# cicely_A_v1.net
KiCad netlist of a schematic drawn in EAGLE
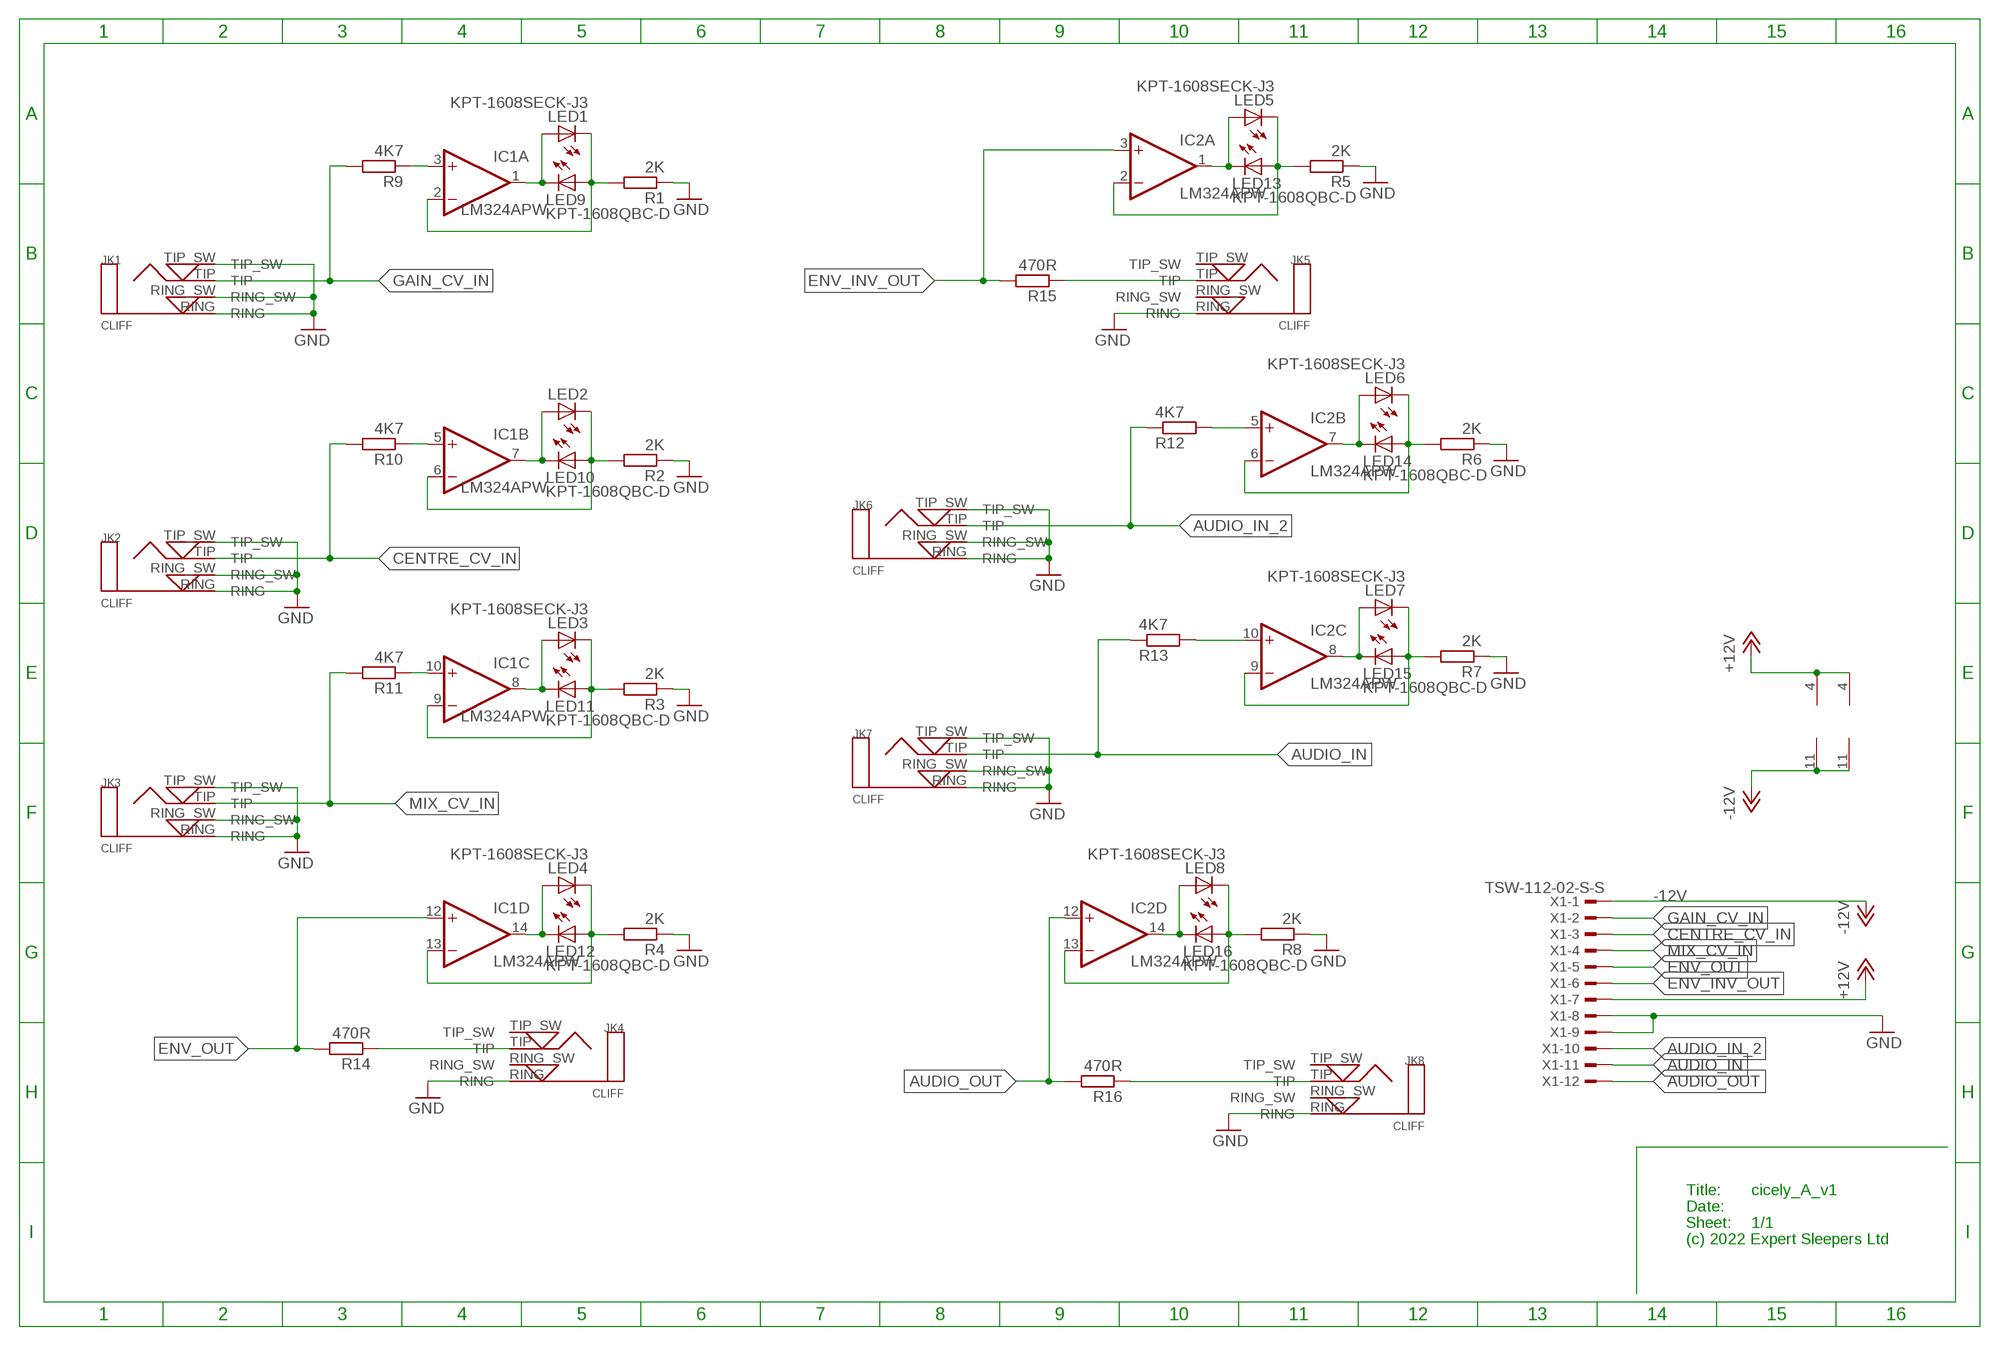
[diagram p0: schematic, sheet 1]

(export (version "E")
  (design (tool "Eeschema 10.0.6"))
  (components
    (comp (ref "IC1")
      (value "LM324APW")
      (footprint "eagle-import:PW_R-PDSO-G14")
      (libsource (lib "eagle-import") (part "TL074PW"))
    )
    (comp (ref "IC2")
      (value "LM324APW")
      (footprint "eagle-import:PW_R-PDSO-G14")
      (libsource (lib "eagle-import") (part "TL074PW"))
    )
    (comp (ref "JK1")
      (value "CLIFF")
      (footprint "eagle-import:CLIFF3.5MMPCB")
      (libsource (lib "eagle-import") (part "CLIFF3.5MM_PCB_SW_JK"))
    )
    (comp (ref "JK2")
      (value "CLIFF")
      (footprint "eagle-import:CLIFF3.5MMPCB")
      (libsource (lib "eagle-import") (part "CLIFF3.5MM_PCB_SW_JK"))
    )
    (comp (ref "JK3")
      (value "CLIFF")
      (footprint "eagle-import:CLIFF3.5MMPCB")
      (libsource (lib "eagle-import") (part "CLIFF3.5MM_PCB_SW_JK"))
    )
    (comp (ref "JK4")
      (value "CLIFF")
      (footprint "eagle-import:CLIFF3.5MMPCB")
      (libsource (lib "eagle-import") (part "CLIFF3.5MM_PCB_SW_JK"))
    )
    (comp (ref "JK5")
      (value "CLIFF")
      (footprint "eagle-import:CLIFF3.5MMPCB")
      (libsource (lib "eagle-import") (part "CLIFF3.5MM_PCB_SW_JK"))
    )
    (comp (ref "JK6")
      (value "CLIFF")
      (footprint "eagle-import:CLIFF3.5MMPCB")
      (libsource (lib "eagle-import") (part "CLIFF3.5MM_PCB_SW_JK"))
    )
    (comp (ref "JK7")
      (value "CLIFF")
      (footprint "eagle-import:CLIFF3.5MMPCB")
      (libsource (lib "eagle-import") (part "CLIFF3.5MM_PCB_SW_JK"))
    )
    (comp (ref "JK8")
      (value "CLIFF")
      (footprint "eagle-import:CLIFF3.5MMPCB")
      (libsource (lib "eagle-import") (part "CLIFF3.5MM_PCB_SW_JK"))
    )
    (comp (ref "LED1")
      (value "KPT-1608SECK-J3")
      (footprint "eagle-import:CHIPLED_0603_LEFT")
      (libsource (lib "eagle-import") (part "KPT-1608SECK-J3"))
    )
    (comp (ref "LED2")
      (value "KPT-1608SECK-J3")
      (footprint "eagle-import:CHIPLED_0603_LEFT")
      (libsource (lib "eagle-import") (part "KPT-1608SECK-J3"))
    )
    (comp (ref "LED3")
      (value "KPT-1608SECK-J3")
      (footprint "eagle-import:CHIPLED_0603_LEFT")
      (libsource (lib "eagle-import") (part "KPT-1608SECK-J3"))
    )
    (comp (ref "LED4")
      (value "KPT-1608SECK-J3")
      (footprint "eagle-import:CHIPLED_0603_LEFT")
      (libsource (lib "eagle-import") (part "KPT-1608SECK-J3"))
    )
    (comp (ref "LED5")
      (value "KPT-1608SECK-J3")
      (footprint "eagle-import:CHIPLED_0603_LEFT")
      (libsource (lib "eagle-import") (part "KPT-1608SECK-J3"))
    )
    (comp (ref "LED6")
      (value "KPT-1608SECK-J3")
      (footprint "eagle-import:CHIPLED_0603_LEFT")
      (libsource (lib "eagle-import") (part "KPT-1608SECK-J3"))
    )
    (comp (ref "LED7")
      (value "KPT-1608SECK-J3")
      (footprint "eagle-import:CHIPLED_0603_LEFT")
      (libsource (lib "eagle-import") (part "KPT-1608SECK-J3"))
    )
    (comp (ref "LED8")
      (value "KPT-1608SECK-J3")
      (footprint "eagle-import:CHIPLED_0603_LEFT")
      (libsource (lib "eagle-import") (part "KPT-1608SECK-J3"))
    )
    (comp (ref "LED9")
      (value "KPT-1608QBC-D")
      (footprint "eagle-import:CHIPLED_0603_RIGHT")
      (libsource (lib "eagle-import") (part "KPT-1608QBC-D"))
    )
    (comp (ref "LED10")
      (value "KPT-1608QBC-D")
      (footprint "eagle-import:CHIPLED_0603_RIGHT")
      (libsource (lib "eagle-import") (part "KPT-1608QBC-D"))
    )
    (comp (ref "LED11")
      (value "KPT-1608QBC-D")
      (footprint "eagle-import:CHIPLED_0603_RIGHT")
      (libsource (lib "eagle-import") (part "KPT-1608QBC-D"))
    )
    (comp (ref "LED12")
      (value "KPT-1608QBC-D")
      (footprint "eagle-import:CHIPLED_0603_RIGHT")
      (libsource (lib "eagle-import") (part "KPT-1608QBC-D"))
    )
    (comp (ref "LED13")
      (value "KPT-1608QBC-D")
      (footprint "eagle-import:CHIPLED_0603_RIGHT")
      (libsource (lib "eagle-import") (part "KPT-1608QBC-D"))
    )
    (comp (ref "LED14")
      (value "KPT-1608QBC-D")
      (footprint "eagle-import:CHIPLED_0603_RIGHT")
      (libsource (lib "eagle-import") (part "KPT-1608QBC-D"))
    )
    (comp (ref "LED15")
      (value "KPT-1608QBC-D")
      (footprint "eagle-import:CHIPLED_0603_RIGHT")
      (libsource (lib "eagle-import") (part "KPT-1608QBC-D"))
    )
    (comp (ref "LED16")
      (value "KPT-1608QBC-D")
      (footprint "eagle-import:CHIPLED_0603_RIGHT")
      (libsource (lib "eagle-import") (part "KPT-1608QBC-D"))
    )
    (comp (ref "R1")
      (value "2K")
      (footprint "eagle-import:R1206")
      (libsource (lib "eagle-import") (part "R-EU_R1206"))
    )
    (comp (ref "R2")
      (value "2K")
      (footprint "eagle-import:R1206")
      (libsource (lib "eagle-import") (part "R-EU_R1206"))
    )
    (comp (ref "R3")
      (value "2K")
      (footprint "eagle-import:R1206")
      (libsource (lib "eagle-import") (part "R-EU_R1206"))
    )
    (comp (ref "R4")
      (value "2K")
      (footprint "eagle-import:R1206")
      (libsource (lib "eagle-import") (part "R-EU_R1206"))
    )
    (comp (ref "R5")
      (value "2K")
      (footprint "eagle-import:R1206")
      (libsource (lib "eagle-import") (part "R-EU_R1206"))
    )
    (comp (ref "R6")
      (value "2K")
      (footprint "eagle-import:R1206")
      (libsource (lib "eagle-import") (part "R-EU_R1206"))
    )
    (comp (ref "R7")
      (value "2K")
      (footprint "eagle-import:R1206")
      (libsource (lib "eagle-import") (part "R-EU_R1206"))
    )
    (comp (ref "R8")
      (value "2K")
      (footprint "eagle-import:R1206")
      (libsource (lib "eagle-import") (part "R-EU_R1206"))
    )
    (comp (ref "R9")
      (value "4K7")
      (footprint "eagle-import:R1206")
      (libsource (lib "eagle-import") (part "R-EU_R1206"))
    )
    (comp (ref "R10")
      (value "4K7")
      (footprint "eagle-import:R1206")
      (libsource (lib "eagle-import") (part "R-EU_R1206"))
    )
    (comp (ref "R11")
      (value "4K7")
      (footprint "eagle-import:R1206")
      (libsource (lib "eagle-import") (part "R-EU_R1206"))
    )
    (comp (ref "R12")
      (value "4K7")
      (footprint "eagle-import:R1206")
      (libsource (lib "eagle-import") (part "R-EU_R1206"))
    )
    (comp (ref "R13")
      (value "4K7")
      (footprint "eagle-import:R1206")
      (libsource (lib "eagle-import") (part "R-EU_R1206"))
    )
    (comp (ref "R14")
      (value "470R")
      (footprint "eagle-import:R1206")
      (libsource (lib "eagle-import") (part "R-EU_R1206"))
    )
    (comp (ref "R15")
      (value "470R")
      (footprint "eagle-import:R1206")
      (libsource (lib "eagle-import") (part "R-EU_R1206"))
    )
    (comp (ref "R16")
      (value "470R")
      (footprint "eagle-import:R1206")
      (libsource (lib "eagle-import") (part "R-EU_R1206"))
    )
    (comp (ref "X1")
      (value "TSW-112-02-S-S")
      (footprint "eagle-import:TSW-112-02-S-S")
      (libsource (lib "eagle-import") (part "TSW-112-02-S-S"))
    )
  )
  (nets
    (net (code "1") (name "+12V") (class "Default")
      (node (ref "IC1") (pin "4") (pinfunction "V+_4") (pintype "power_in"))
      (node (ref "IC2") (pin "4") (pinfunction "V+_4") (pintype "power_in"))
      (node (ref "X1") (pin "7") (pinfunction "1_7") (pintype "passive"))
    )
    (net (code "2") (name "-12V") (class "Default")
      (node (ref "IC1") (pin "11") (pinfunction "V-_11") (pintype "power_in"))
      (node (ref "IC2") (pin "11") (pinfunction "V-_11") (pintype "power_in"))
      (node (ref "X1") (pin "1") (pinfunction "1_1") (pintype "passive"))
    )
    (net (code "3") (name "AUDIO_IN") (class "Default")
      (node (ref "JK7") (pin "TIP") (pinfunction "TIP_TIP") (pintype "bidirectional"))
      (node (ref "R13") (pin "1") (pinfunction "1_1") (pintype "passive"))
      (node (ref "X1") (pin "11") (pinfunction "1_11") (pintype "passive"))
    )
    (net (code "4") (name "AUDIO_IN_2") (class "Default")
      (node (ref "JK6") (pin "TIP") (pinfunction "TIP_TIP") (pintype "bidirectional"))
      (node (ref "R12") (pin "1") (pinfunction "1_1") (pintype "passive"))
      (node (ref "X1") (pin "10") (pinfunction "1_10") (pintype "passive"))
    )
    (net (code "5") (name "AUDIO_OUT") (class "Default")
      (node (ref "IC2") (pin "12") (pinfunction "+IN_12") (pintype "input"))
      (node (ref "R16") (pin "2") (pinfunction "2_2") (pintype "passive"))
      (node (ref "X1") (pin "12") (pinfunction "1_12") (pintype "passive"))
    )
    (net (code "6") (name "CENTRE_CV_IN") (class "Default")
      (node (ref "JK2") (pin "TIP") (pinfunction "TIP_TIP") (pintype "bidirectional"))
      (node (ref "R10") (pin "2") (pinfunction "2_2") (pintype "passive"))
      (node (ref "X1") (pin "3") (pinfunction "1_3") (pintype "passive"))
    )
    (net (code "7") (name "ENV_INV_OUT") (class "Default")
      (node (ref "IC2") (pin "3") (pinfunction "+IN_3") (pintype "input"))
      (node (ref "R15") (pin "2") (pinfunction "2_2") (pintype "passive"))
      (node (ref "X1") (pin "6") (pinfunction "1_6") (pintype "passive"))
    )
    (net (code "8") (name "ENV_OUT") (class "Default")
      (node (ref "IC1") (pin "12") (pinfunction "+IN_12") (pintype "input"))
      (node (ref "R14") (pin "2") (pinfunction "2_2") (pintype "passive"))
      (node (ref "X1") (pin "5") (pinfunction "1_5") (pintype "passive"))
    )
    (net (code "9") (name "GAIN_CV_IN") (class "Default")
      (node (ref "JK1") (pin "TIP") (pinfunction "TIP_TIP") (pintype "bidirectional"))
      (node (ref "R9") (pin "2") (pinfunction "2_2") (pintype "passive"))
      (node (ref "X1") (pin "2") (pinfunction "1_2") (pintype "passive"))
    )
    (net (code "10") (name "GND") (class "Default")
      (node (ref "JK1") (pin "RING") (pinfunction "RING_RING") (pintype "bidirectional"))
      (node (ref "JK1") (pin "RING_SW") (pinfunction "RING_SW_RING_SW") (pintype "bidirectional"))
      (node (ref "JK1") (pin "TIP_SW") (pinfunction "TIP_SW_TIP_SW") (pintype "bidirectional"))
      (node (ref "JK2") (pin "RING") (pinfunction "RING_RING") (pintype "bidirectional"))
      (node (ref "JK2") (pin "RING_SW") (pinfunction "RING_SW_RING_SW") (pintype "bidirectional"))
      (node (ref "JK2") (pin "TIP_SW") (pinfunction "TIP_SW_TIP_SW") (pintype "bidirectional"))
      (node (ref "JK3") (pin "RING") (pinfunction "RING_RING") (pintype "bidirectional"))
      (node (ref "JK3") (pin "RING_SW") (pinfunction "RING_SW_RING_SW") (pintype "bidirectional"))
      (node (ref "JK3") (pin "TIP_SW") (pinfunction "TIP_SW_TIP_SW") (pintype "bidirectional"))
      (node (ref "JK4") (pin "RING") (pinfunction "RING_RING") (pintype "bidirectional"))
      (node (ref "JK5") (pin "RING") (pinfunction "RING_RING") (pintype "bidirectional"))
      (node (ref "JK6") (pin "RING") (pinfunction "RING_RING") (pintype "bidirectional"))
      (node (ref "JK6") (pin "RING_SW") (pinfunction "RING_SW_RING_SW") (pintype "bidirectional"))
      (node (ref "JK6") (pin "TIP_SW") (pinfunction "TIP_SW_TIP_SW") (pintype "bidirectional"))
      (node (ref "JK7") (pin "RING") (pinfunction "RING_RING") (pintype "bidirectional"))
      (node (ref "JK7") (pin "RING_SW") (pinfunction "RING_SW_RING_SW") (pintype "bidirectional"))
      (node (ref "JK7") (pin "TIP_SW") (pinfunction "TIP_SW_TIP_SW") (pintype "bidirectional"))
      (node (ref "JK8") (pin "RING") (pinfunction "RING_RING") (pintype "bidirectional"))
      (node (ref "R1") (pin "1") (pinfunction "1_1") (pintype "passive"))
      (node (ref "R2") (pin "1") (pinfunction "1_1") (pintype "passive"))
      (node (ref "R3") (pin "1") (pinfunction "1_1") (pintype "passive"))
      (node (ref "R4") (pin "1") (pinfunction "1_1") (pintype "passive"))
      (node (ref "R5") (pin "1") (pinfunction "1_1") (pintype "passive"))
      (node (ref "R6") (pin "1") (pinfunction "1_1") (pintype "passive"))
      (node (ref "R7") (pin "1") (pinfunction "1_1") (pintype "passive"))
      (node (ref "R8") (pin "1") (pinfunction "1_1") (pintype "passive"))
      (node (ref "X1") (pin "8") (pinfunction "1_8") (pintype "passive"))
      (node (ref "X1") (pin "9") (pinfunction "1_9") (pintype "passive"))
    )
    (net (code "11") (name "MIX_CV_IN") (class "Default")
      (node (ref "JK3") (pin "TIP") (pinfunction "TIP_TIP") (pintype "bidirectional"))
      (node (ref "R11") (pin "2") (pinfunction "2_2") (pintype "passive"))
      (node (ref "X1") (pin "4") (pinfunction "1_4") (pintype "passive"))
    )
    (net (code "12") (name "Net-(IC1A-+IN)") (class "Default")
      (node (ref "IC1") (pin "3") (pinfunction "+IN_3") (pintype "input"))
      (node (ref "R9") (pin "1") (pinfunction "1_1") (pintype "passive"))
    )
    (net (code "13") (name "Net-(IC1A--IN)") (class "Default")
      (node (ref "IC1") (pin "2") (pinfunction "-IN_2") (pintype "input"))
      (node (ref "LED1") (pin "1") (pinfunction "C_1") (pintype "passive"))
      (node (ref "LED9") (pin "1") (pinfunction "A_1") (pintype "passive"))
      (node (ref "R1") (pin "2") (pinfunction "2_2") (pintype "passive"))
    )
    (net (code "14") (name "Net-(IC1A-OUT)") (class "Default")
      (node (ref "IC1") (pin "1") (pinfunction "OUT_1") (pintype "output"))
      (node (ref "LED1") (pin "2") (pinfunction "A_2") (pintype "passive"))
      (node (ref "LED9") (pin "2") (pinfunction "C_2") (pintype "passive"))
    )
    (net (code "15") (name "Net-(IC1B-+IN)") (class "Default")
      (node (ref "IC1") (pin "5") (pinfunction "+IN_5") (pintype "input"))
      (node (ref "R10") (pin "1") (pinfunction "1_1") (pintype "passive"))
    )
    (net (code "16") (name "Net-(IC1B--IN)") (class "Default")
      (node (ref "IC1") (pin "6") (pinfunction "-IN_6") (pintype "input"))
      (node (ref "LED10") (pin "1") (pinfunction "A_1") (pintype "passive"))
      (node (ref "LED2") (pin "1") (pinfunction "C_1") (pintype "passive"))
      (node (ref "R2") (pin "2") (pinfunction "2_2") (pintype "passive"))
    )
    (net (code "17") (name "Net-(IC1B-OUT)") (class "Default")
      (node (ref "IC1") (pin "7") (pinfunction "OUT_7") (pintype "output"))
      (node (ref "LED10") (pin "2") (pinfunction "C_2") (pintype "passive"))
      (node (ref "LED2") (pin "2") (pinfunction "A_2") (pintype "passive"))
    )
    (net (code "18") (name "Net-(IC1C-+IN)") (class "Default")
      (node (ref "IC1") (pin "10") (pinfunction "+IN_10") (pintype "input"))
      (node (ref "R11") (pin "1") (pinfunction "1_1") (pintype "passive"))
    )
    (net (code "19") (name "Net-(IC1C--IN)") (class "Default")
      (node (ref "IC1") (pin "9") (pinfunction "-IN_9") (pintype "input"))
      (node (ref "LED11") (pin "1") (pinfunction "A_1") (pintype "passive"))
      (node (ref "LED3") (pin "1") (pinfunction "C_1") (pintype "passive"))
      (node (ref "R3") (pin "2") (pinfunction "2_2") (pintype "passive"))
    )
    (net (code "20") (name "Net-(IC1C-OUT)") (class "Default")
      (node (ref "IC1") (pin "8") (pinfunction "OUT_8") (pintype "output"))
      (node (ref "LED11") (pin "2") (pinfunction "C_2") (pintype "passive"))
      (node (ref "LED3") (pin "2") (pinfunction "A_2") (pintype "passive"))
    )
    (net (code "21") (name "Net-(IC1D--IN)") (class "Default")
      (node (ref "IC1") (pin "13") (pinfunction "-IN_13") (pintype "input"))
      (node (ref "LED12") (pin "1") (pinfunction "A_1") (pintype "passive"))
      (node (ref "LED4") (pin "1") (pinfunction "C_1") (pintype "passive"))
      (node (ref "R4") (pin "2") (pinfunction "2_2") (pintype "passive"))
    )
    (net (code "22") (name "Net-(IC1D-OUT)") (class "Default")
      (node (ref "IC1") (pin "14") (pinfunction "OUT_14") (pintype "output"))
      (node (ref "LED12") (pin "2") (pinfunction "C_2") (pintype "passive"))
      (node (ref "LED4") (pin "2") (pinfunction "A_2") (pintype "passive"))
    )
    (net (code "23") (name "Net-(IC2A--IN)") (class "Default")
      (node (ref "IC2") (pin "2") (pinfunction "-IN_2") (pintype "input"))
      (node (ref "LED13") (pin "1") (pinfunction "A_1") (pintype "passive"))
      (node (ref "LED5") (pin "1") (pinfunction "C_1") (pintype "passive"))
      (node (ref "R5") (pin "2") (pinfunction "2_2") (pintype "passive"))
    )
    (net (code "24") (name "Net-(IC2A-OUT)") (class "Default")
      (node (ref "IC2") (pin "1") (pinfunction "OUT_1") (pintype "output"))
      (node (ref "LED13") (pin "2") (pinfunction "C_2") (pintype "passive"))
      (node (ref "LED5") (pin "2") (pinfunction "A_2") (pintype "passive"))
    )
    (net (code "25") (name "Net-(IC2B-+IN)") (class "Default")
      (node (ref "IC2") (pin "5") (pinfunction "+IN_5") (pintype "input"))
      (node (ref "R12") (pin "2") (pinfunction "2_2") (pintype "passive"))
    )
    (net (code "26") (name "Net-(IC2B--IN)") (class "Default")
      (node (ref "IC2") (pin "6") (pinfunction "-IN_6") (pintype "input"))
      (node (ref "LED14") (pin "1") (pinfunction "A_1") (pintype "passive"))
      (node (ref "LED6") (pin "1") (pinfunction "C_1") (pintype "passive"))
      (node (ref "R6") (pin "2") (pinfunction "2_2") (pintype "passive"))
    )
    (net (code "27") (name "Net-(IC2B-OUT)") (class "Default")
      (node (ref "IC2") (pin "7") (pinfunction "OUT_7") (pintype "output"))
      (node (ref "LED14") (pin "2") (pinfunction "C_2") (pintype "passive"))
      (node (ref "LED6") (pin "2") (pinfunction "A_2") (pintype "passive"))
    )
    (net (code "28") (name "Net-(IC2C-+IN)") (class "Default")
      (node (ref "IC2") (pin "10") (pinfunction "+IN_10") (pintype "input"))
      (node (ref "R13") (pin "2") (pinfunction "2_2") (pintype "passive"))
    )
    (net (code "29") (name "Net-(IC2C--IN)") (class "Default")
      (node (ref "IC2") (pin "9") (pinfunction "-IN_9") (pintype "input"))
      (node (ref "LED15") (pin "1") (pinfunction "A_1") (pintype "passive"))
      (node (ref "LED7") (pin "1") (pinfunction "C_1") (pintype "passive"))
      (node (ref "R7") (pin "2") (pinfunction "2_2") (pintype "passive"))
    )
    (net (code "30") (name "Net-(IC2C-OUT)") (class "Default")
      (node (ref "IC2") (pin "8") (pinfunction "OUT_8") (pintype "output"))
      (node (ref "LED15") (pin "2") (pinfunction "C_2") (pintype "passive"))
      (node (ref "LED7") (pin "2") (pinfunction "A_2") (pintype "passive"))
    )
    (net (code "31") (name "Net-(IC2D--IN)") (class "Default")
      (node (ref "IC2") (pin "13") (pinfunction "-IN_13") (pintype "input"))
      (node (ref "LED16") (pin "1") (pinfunction "A_1") (pintype "passive"))
      (node (ref "LED8") (pin "1") (pinfunction "C_1") (pintype "passive"))
      (node (ref "R8") (pin "2") (pinfunction "2_2") (pintype "passive"))
    )
    (net (code "32") (name "Net-(IC2D-OUT)") (class "Default")
      (node (ref "IC2") (pin "14") (pinfunction "OUT_14") (pintype "output"))
      (node (ref "LED16") (pin "2") (pinfunction "C_2") (pintype "passive"))
      (node (ref "LED8") (pin "2") (pinfunction "A_2") (pintype "passive"))
    )
    (net (code "33") (name "Net-(JK4-PadTIP)") (class "Default")
      (node (ref "JK4") (pin "TIP") (pinfunction "TIP_TIP") (pintype "bidirectional"))
      (node (ref "R14") (pin "1") (pinfunction "1_1") (pintype "passive"))
    )
    (net (code "34") (name "Net-(JK5-PadTIP)") (class "Default")
      (node (ref "JK5") (pin "TIP") (pinfunction "TIP_TIP") (pintype "bidirectional"))
      (node (ref "R15") (pin "1") (pinfunction "1_1") (pintype "passive"))
    )
    (net (code "35") (name "Net-(JK8-PadTIP)") (class "Default")
      (node (ref "JK8") (pin "TIP") (pinfunction "TIP_TIP") (pintype "bidirectional"))
      (node (ref "R16") (pin "1") (pinfunction "1_1") (pintype "passive"))
    )
    (net (code "36") (name "unconnected-(JK4-PadRING_SW)") (class "Default")
      (node (ref "JK4") (pin "RING_SW") (pinfunction "RING_SW_RING_SW") (pintype "bidirectional"))
    )
    (net (code "37") (name "unconnected-(JK4-PadTIP_SW)") (class "Default")
      (node (ref "JK4") (pin "TIP_SW") (pinfunction "TIP_SW_TIP_SW") (pintype "bidirectional"))
    )
    (net (code "38") (name "unconnected-(JK5-PadRING_SW)") (class "Default")
      (node (ref "JK5") (pin "RING_SW") (pinfunction "RING_SW_RING_SW") (pintype "bidirectional"))
    )
    (net (code "39") (name "unconnected-(JK5-PadTIP_SW)") (class "Default")
      (node (ref "JK5") (pin "TIP_SW") (pinfunction "TIP_SW_TIP_SW") (pintype "bidirectional"))
    )
    (net (code "40") (name "unconnected-(JK8-PadRING_SW)") (class "Default")
      (node (ref "JK8") (pin "RING_SW") (pinfunction "RING_SW_RING_SW") (pintype "bidirectional"))
    )
    (net (code "41") (name "unconnected-(JK8-PadTIP_SW)") (class "Default")
      (node (ref "JK8") (pin "TIP_SW") (pinfunction "TIP_SW_TIP_SW") (pintype "bidirectional"))
    )
  )
)
